# encoder.net
KiCad netlist of a schematic drawn in Altium Designer
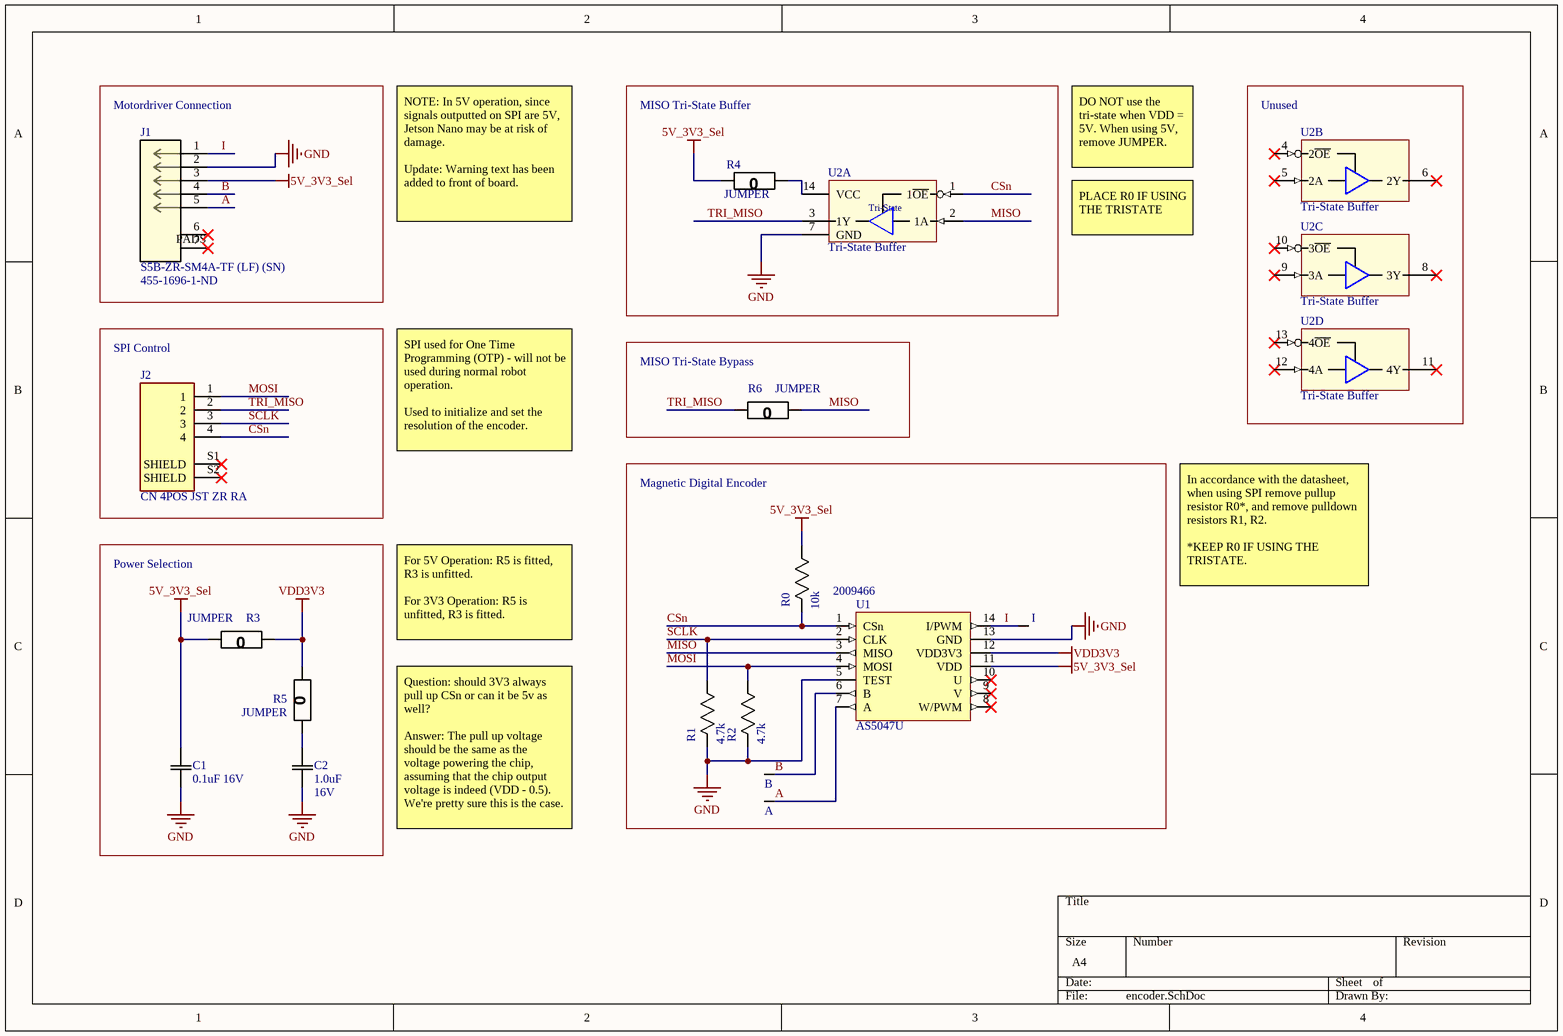
[diagram p0: encoder.SchDoc]

(export (version "E")
  (design (tool "Eeschema 10.0.6"))
  (components
    (comp (ref "A")
      (value "Test Point (Via)")
      (footprint "TP")
      (libsource (lib "IC_Library") (part "Test Point (Via)"))
    )
    (comp (ref "B")
      (value "Test Point (Via)")
      (footprint "TP")
      (libsource (lib "IC_Library") (part "Test Point (Via)"))
    )
    (comp (ref "C1")
      (value "0.1uF 16V")
      (footprint "0603")
      (description "Default Symbol for Capacitors")
      (fields (field (name "PART NUMBER") "CAP 0.10uF 16V") (field (name "TOLERANCE") "10%"))
      (libsource (lib "capacitor_library") (part "CAP_Default"))
    )
    (comp (ref "C2")
      (value "1.0uF")
      (footprint "0603")
      (description "Default Symbol for Capacitors")
      (fields
        (field (name "TOLERANCE") "10%")
        (field (name "RATING") "16V")
        (field (name "PART NUMBER") "CAP 1.0uF 16V")
      )
      (libsource (lib "Capacitor_Library") (part "CAP_Default"))
    )
    (comp (ref "I")
      (value "Test Point (Via)")
      (footprint "TP")
      (libsource (lib "IC_Library") (part "Test Point (Via)"))
    )
    (comp (ref "J1")
      (value "S5B-ZR-SM4A-TF (LF) (SN)")
      (footprint "JST_S5B-ZR-SM4A-TF")
      (description "Connector Header Surface Mount, Right Angle 5 position 0.059\" (1.50mm)")
      (fields
        (field (name "SUPPLIER PART NUMBER 1") "455-1696-1-ND")
        (field (name "PART NUMBER") "CN 5POS JST ZR RA")
      )
      (libsource (lib "Connector_Library") (part "CN 5POS JST ZR RA"))
    )
    (comp (ref "J2")
      (value "CN 4POS JST ZR RA")
      (footprint "JST_S4B-ZR-SM4A-TF(LF)(SN)")
      (description "Connector Header Surface Mount, Right Angle 4 position 0.059 (1.50mm)")
      (fields (field (name "MF") "JST Sales") (field (name "MP") "S4B-ZR-SM4A-TF(LF)(SN)"))
      (libsource (lib "Connector_Library") (part "CN 4POS JST ZR RA"))
    )
    (comp (ref "R0")
      (value "10k")
      (footprint "0603")
      (description "Default Resistor Symbol")
      (fields (field (name "TOLERANCE") "5%") (field (name "PART NUMBER") "RES 10k 1/8W - 1%"))
      (libsource (lib "Resistor_Library") (part "RES_DEFAULT"))
    )
    (comp (ref "R1")
      (value "4.7k")
      (footprint "0603")
      (description "Default Resistor Symbol")
      (fields (field (name "TOLERANCE") "1%") (field (name "PART NUMBER") "RES 4.7k 1/8W - 1%"))
      (libsource (lib "Resistor_Library") (part "RES_DEFAULT"))
    )
    (comp (ref "R2")
      (value "4.7k")
      (footprint "0603")
      (description "Default Resistor Symbol")
      (fields (field (name "TOLERANCE") "1%") (field (name "PART NUMBER") "RES 4.7k 1/8W - 1%"))
      (libsource (lib "") (part "RES_DEFAULT_1"))
    )
    (comp (ref "R3")
      (value "JUMPER")
      (footprint "0603")
      (description "RES SMD 0 OHM JUMPER GENERIC 0805")
      (fields (field (name "PART NUMBER") "RES 0 JUMPER"))
      (libsource (lib "Resistor_Library") (part "RES 0 JUMPER"))
    )
    (comp (ref "R4")
      (value "JUMPER")
      (footprint "0603")
      (description "RES SMD 0 OHM JUMPER GENERIC 0805")
      (fields (field (name "PART NUMBER") "RES 0 JUMPER"))
      (libsource (lib "Resistor_Library") (part "RES 0 JUMPER"))
    )
    (comp (ref "R5")
      (value "JUMPER")
      (footprint "0603")
      (description "RES SMD 0 OHM JUMPER GENERIC 0805")
      (fields (field (name "PART NUMBER") "RES 0 JUMPER"))
      (libsource (lib "Resistor_Library") (part "RES 0 JUMPER"))
    )
    (comp (ref "R6")
      (value "JUMPER")
      (footprint "0603")
      (description "RES SMD 0 OHM JUMPER GENERIC 0805")
      (fields (field (name "PART NUMBER") "RES 0 JUMPER"))
      (libsource (lib "Resistor_Library") (part "RES 0 JUMPER"))
    )
    (comp (ref "U1")
      (value "AS5047U")
      (footprint "AS5047U")
      (description "14-Bit On-Axis Magnetic Rotary Position Sensor with Up to 14-Bit Binary Incremental Pulse Count")
      (fields (field (name "SUPPLIER PART NUMBER 1") "2009466"))
      (libsource (lib "AltiumLibraries") (part "AS5047U"))
    )
    (comp (ref "U2")
      (value "Tri-State Buffer")
      (footprint "14-TSSOP")
      (description "Buffer, Non-Inverting 4 Element 1 Bit per Element 3-State Output 14-TSSOP")
      (fields (field (name "PART NUMBER") "SN74LVC125APWR"))
      (libsource (lib "IC_Library") (part "SN74LVC125APWR"))
    )
  )
  (nets
    (net (code "1") (name "/A") (class "Default")
      (node (ref "A") (pin "1") (pinfunction "1_1") (pintype "passive"))
      (node (ref "J1") (pin "5") (pinfunction "5_5") (pintype "passive"))
      (node (ref "U1") (pin "7") (pinfunction "A_7") (pintype "output"))
    )
    (net (code "2") (name "/B") (class "Default")
      (node (ref "B") (pin "1") (pinfunction "1_1") (pintype "passive"))
      (node (ref "J1") (pin "4") (pinfunction "4_4") (pintype "passive"))
      (node (ref "U1") (pin "6") (pinfunction "B_6") (pintype "output"))
    )
    (net (code "3") (name "/CSn") (class "Default")
      (node (ref "J2") (pin "4") (pinfunction "4_4") (pintype "passive"))
      (node (ref "R0") (pin "2") (pinfunction "R2_2") (pintype "passive"))
      (node (ref "U1") (pin "1") (pinfunction "CSn_1") (pintype "input"))
      (node (ref "U2") (pin "1") (pinfunction "1~{OE}_1") (pintype "input"))
    )
    (net (code "4") (name "/I") (class "Default")
      (node (ref "I") (pin "1") (pinfunction "1_1") (pintype "passive"))
      (node (ref "J1") (pin "1") (pinfunction "1_1") (pintype "passive"))
      (node (ref "U1") (pin "14") (pinfunction "I/PWM_14") (pintype "output"))
    )
    (net (code "5") (name "/MISO") (class "Default")
      (node (ref "R6") (pin "1") (pinfunction "R1_1") (pintype "passive"))
      (node (ref "U1") (pin "3") (pinfunction "MISO_3") (pintype "output"))
      (node (ref "U2") (pin "2") (pinfunction "1A_2") (pintype "input"))
    )
    (net (code "6") (name "/MOSI") (class "Default")
      (node (ref "J2") (pin "1") (pinfunction "1_1") (pintype "passive"))
      (node (ref "R2") (pin "1") (pinfunction "R1_1") (pintype "passive"))
      (node (ref "U1") (pin "4") (pinfunction "MOSI_4") (pintype "input"))
    )
    (net (code "7") (name "/SCLK") (class "Default")
      (node (ref "J2") (pin "3") (pinfunction "3_3") (pintype "passive"))
      (node (ref "R1") (pin "1") (pinfunction "R1_1") (pintype "passive"))
      (node (ref "U1") (pin "2") (pinfunction "CLK_2") (pintype "input"))
    )
    (net (code "8") (name "/TRI_MISO") (class "Default")
      (node (ref "J2") (pin "2") (pinfunction "2_2") (pintype "passive"))
      (node (ref "R6") (pin "2") (pinfunction "R2_2") (pintype "passive"))
      (node (ref "U2") (pin "3") (pinfunction "1Y_3") (pintype "passive"))
    )
    (net (code "9") (name "5V_3V3_Sel") (class "Default")
      (node (ref "C1") (pin "1") (pinfunction "C1_1") (pintype "passive"))
      (node (ref "J1") (pin "3") (pinfunction "3_3") (pintype "passive"))
      (node (ref "R0") (pin "1") (pinfunction "R1_1") (pintype "passive"))
      (node (ref "R3") (pin "1") (pinfunction "R1_1") (pintype "passive"))
      (node (ref "R4") (pin "2") (pinfunction "R2_2") (pintype "passive"))
      (node (ref "U1") (pin "11") (pinfunction "VDD_11") (pintype "passive"))
    )
    (net (code "10") (name "GND") (class "Default")
      (node (ref "C1") (pin "2") (pinfunction "C2_2") (pintype "passive"))
      (node (ref "C2") (pin "2") (pinfunction "C2_2") (pintype "passive"))
      (node (ref "J1") (pin "2") (pinfunction "2_2") (pintype "passive"))
      (node (ref "R1") (pin "2") (pinfunction "R2_2") (pintype "passive"))
      (node (ref "R2") (pin "2") (pinfunction "R2_2") (pintype "passive"))
      (node (ref "U1") (pin "13") (pinfunction "GND_13") (pintype "passive"))
      (node (ref "U1") (pin "5") (pinfunction "TEST_5") (pintype "passive"))
      (node (ref "U2") (pin "7") (pinfunction "GND_7") (pintype "passive"))
    )
    (net (code "11") (name "Net-(C2-C1)") (class "Default")
      (node (ref "C2") (pin "1") (pinfunction "C1_1") (pintype "passive"))
      (node (ref "R5") (pin "2") (pinfunction "R2_2") (pintype "passive"))
    )
    (net (code "12") (name "Net-(R4-R1)") (class "Default")
      (node (ref "R4") (pin "1") (pinfunction "R1_1") (pintype "passive"))
      (node (ref "U2") (pin "14") (pinfunction "VCC_14") (pintype "passive"))
    )
    (net (code "13") (name "VDD3V3") (class "Default")
      (node (ref "R3") (pin "2") (pinfunction "R2_2") (pintype "passive"))
      (node (ref "R5") (pin "1") (pinfunction "R1_1") (pintype "passive"))
      (node (ref "U1") (pin "12") (pinfunction "VDD3V3_12") (pintype "passive"))
    )
    (net (code "14") (name "unconnected-(J1-Pad6)") (class "Default")
      (node (ref "J1") (pin "6") (pinfunction "6_6") (pintype "passive+no_connect"))
    )
    (net (code "15") (name "unconnected-(J1-Pad7)") (class "Default")
      (node (ref "J1") (pin "7") (pinfunction "7_7") (pintype "passive+no_connect"))
    )
    (net (code "16") (name "unconnected-(J2-SHIELD-PadS1)") (class "Default")
      (node (ref "J2") (pin "S1") (pinfunction "SHIELD_S1") (pintype "passive+no_connect"))
    )
    (net (code "17") (name "unconnected-(J2-SHIELD-PadS2)") (class "Default")
      (node (ref "J2") (pin "S2") (pinfunction "SHIELD_S2") (pintype "passive+no_connect"))
    )
    (net (code "18") (name "unconnected-(U1-U-Pad10)") (class "Default")
      (node (ref "U1") (pin "10") (pinfunction "U_10") (pintype "output+no_connect"))
    )
    (net (code "19") (name "unconnected-(U1-V-Pad9)") (class "Default")
      (node (ref "U1") (pin "9") (pinfunction "V_9") (pintype "output+no_connect"))
    )
    (net (code "20") (name "unconnected-(U1-W{slash}PWM-Pad8)") (class "Default")
      (node (ref "U1") (pin "8") (pinfunction "W/PWM_8") (pintype "output+no_connect"))
    )
    (net (code "21") (name "unconnected-(U2B-2A-Pad5)") (class "Default")
      (node (ref "U2") (pin "5") (pinfunction "2A_5") (pintype "input+no_connect"))
    )
    (net (code "22") (name "unconnected-(U2B-2Y-Pad6)") (class "Default")
      (node (ref "U2") (pin "6") (pinfunction "2Y_6") (pintype "passive+no_connect"))
    )
    (net (code "23") (name "unconnected-(U2B-2~{OE}-Pad4)") (class "Default")
      (node (ref "U2") (pin "4") (pinfunction "2~{OE}_4") (pintype "input+no_connect"))
    )
    (net (code "24") (name "unconnected-(U2C-3A-Pad9)") (class "Default")
      (node (ref "U2") (pin "9") (pinfunction "3A_9") (pintype "input+no_connect"))
    )
    (net (code "25") (name "unconnected-(U2C-3Y-Pad8)") (class "Default")
      (node (ref "U2") (pin "8") (pinfunction "3Y_8") (pintype "passive+no_connect"))
    )
    (net (code "26") (name "unconnected-(U2C-3~{OE}-Pad10)") (class "Default")
      (node (ref "U2") (pin "10") (pinfunction "3~{OE}_10") (pintype "input+no_connect"))
    )
    (net (code "27") (name "unconnected-(U2D-4A-Pad12)") (class "Default")
      (node (ref "U2") (pin "12") (pinfunction "4A_12") (pintype "input+no_connect"))
    )
    (net (code "28") (name "unconnected-(U2D-4Y-Pad11)") (class "Default")
      (node (ref "U2") (pin "11") (pinfunction "4Y_11") (pintype "passive+no_connect"))
    )
    (net (code "29") (name "unconnected-(U2D-4~{OE}-Pad13)") (class "Default")
      (node (ref "U2") (pin "13") (pinfunction "4~{OE}_13") (pintype "input+no_connect"))
    )
  )
)
